# sb-sonata-hyperram.net
KiCad netlist of a schematic drawn in Altium Designer
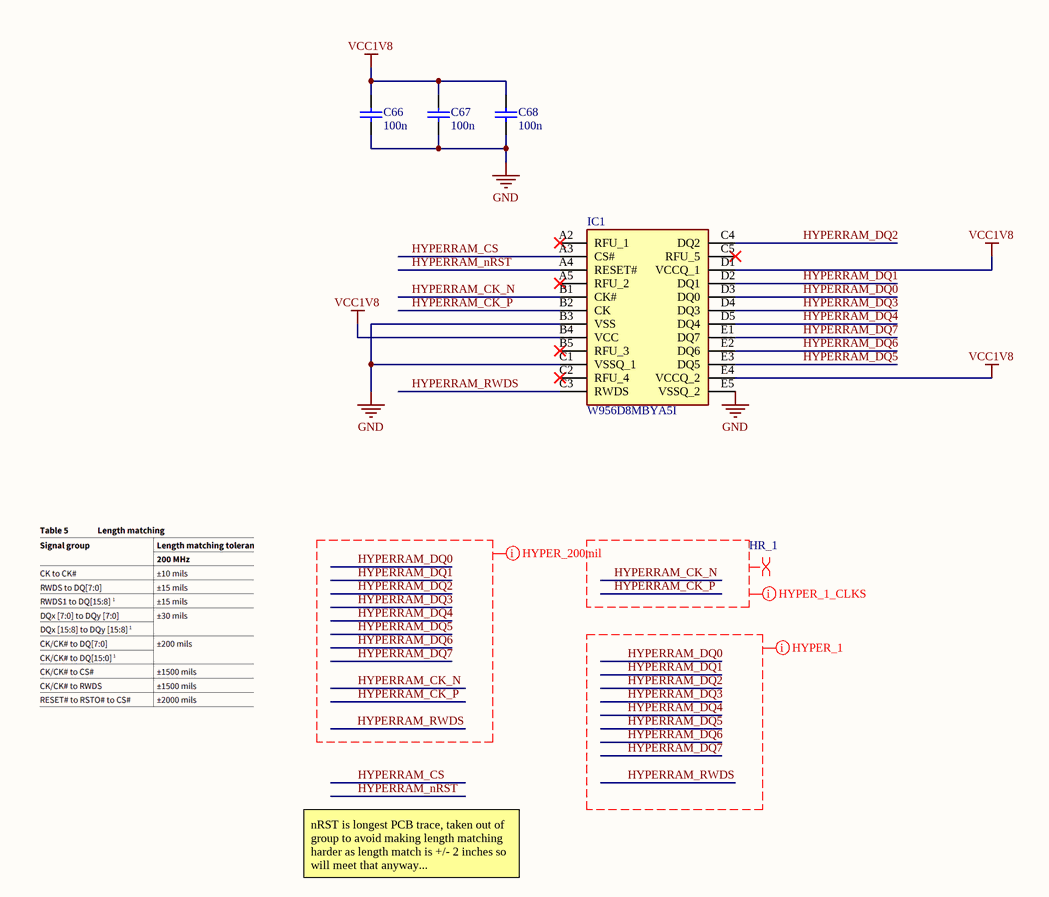
[diagram p0: sb-sonata-hyperram.SchDoc]

(export (version "E")
  (design (tool "Eeschema 10.0.6"))
  (components
    (comp (ref "C66")
      (value "100n")
      (footprint "CAPC0402_M")
      (description "100n, 0402")
      (fields (field (name "PART NUMBER") "CCHIP-100n-0402"))
      (libsource (lib "NewAE_AltiumLib") (part "CAP"))
    )
    (comp (ref "C67")
      (value "100n")
      (footprint "CAPC0402_M")
      (description "100n, 0402")
      (fields (field (name "PART NUMBER") "CCHIP-100n-0402"))
      (libsource (lib "NewAE_AltiumLib") (part "CAP"))
    )
    (comp (ref "C68")
      (value "100n")
      (footprint "CAPC0402_M")
      (description "100n, 0402")
      (fields (field (name "PART NUMBER") "CCHIP-100n-0402"))
      (libsource (lib "NewAE_AltiumLib") (part "CAP"))
    )
    (comp (ref "IC1")
      (value "W956D8MBYA5I")
      (footprint "BGA24C100P5X5_600X800X120")
      (description "Integrated Circuit")
      (fields (field (name "MOUSER PART NUMBER") "454-W956D8MBYA5I"))
      (libsource (lib "*") (part "W956D8MBYA5I"))
    )
  )
  (nets
    (net (code "1") (name "/HYPERRAM_CK_N") (class "Default")
      (node (ref "IC1") (pin "B1") (pinfunction "CK#_B1") (pintype "passive"))
    )
    (net (code "2") (name "/HYPERRAM_CK_P") (class "Default")
      (node (ref "IC1") (pin "B2") (pinfunction "CK_B2") (pintype "passive"))
    )
    (net (code "3") (name "/HYPERRAM_CS") (class "Default")
      (node (ref "IC1") (pin "A3") (pinfunction "CS#_A3") (pintype "passive"))
    )
    (net (code "4") (name "/HYPERRAM_DQ0") (class "Default")
      (node (ref "IC1") (pin "D3") (pinfunction "DQ0_D3") (pintype "passive"))
    )
    (net (code "5") (name "/HYPERRAM_DQ1") (class "Default")
      (node (ref "IC1") (pin "D2") (pinfunction "DQ1_D2") (pintype "passive"))
    )
    (net (code "6") (name "/HYPERRAM_DQ2") (class "Default")
      (node (ref "IC1") (pin "C4") (pinfunction "DQ2_C4") (pintype "passive"))
    )
    (net (code "7") (name "/HYPERRAM_DQ3") (class "Default")
      (node (ref "IC1") (pin "D4") (pinfunction "DQ3_D4") (pintype "passive"))
    )
    (net (code "8") (name "/HYPERRAM_DQ4") (class "Default")
      (node (ref "IC1") (pin "D5") (pinfunction "DQ4_D5") (pintype "passive"))
    )
    (net (code "9") (name "/HYPERRAM_DQ5") (class "Default")
      (node (ref "IC1") (pin "E3") (pinfunction "DQ5_E3") (pintype "passive"))
    )
    (net (code "10") (name "/HYPERRAM_DQ6") (class "Default")
      (node (ref "IC1") (pin "E2") (pinfunction "DQ6_E2") (pintype "passive"))
    )
    (net (code "11") (name "/HYPERRAM_DQ7") (class "Default")
      (node (ref "IC1") (pin "E1") (pinfunction "DQ7_E1") (pintype "passive"))
    )
    (net (code "12") (name "/HYPERRAM_RWDS") (class "Default")
      (node (ref "IC1") (pin "C3") (pinfunction "RWDS_C3") (pintype "passive"))
    )
    (net (code "13") (name "/HYPERRAM_nRST") (class "Default")
      (node (ref "IC1") (pin "A4") (pinfunction "RESET#_A4") (pintype "passive"))
    )
    (net (code "14") (name "GND") (class "Default")
      (node (ref "C66") (pin "2") (pinfunction "2_2") (pintype "passive"))
      (node (ref "C67") (pin "2") (pinfunction "2_2") (pintype "passive"))
      (node (ref "C68") (pin "2") (pinfunction "2_2") (pintype "passive"))
      (node (ref "IC1") (pin "B3") (pinfunction "VSS_B3") (pintype "passive"))
      (node (ref "IC1") (pin "C1") (pinfunction "VSSQ_1_C1") (pintype "passive"))
      (node (ref "IC1") (pin "E5") (pinfunction "VSSQ_2_E5") (pintype "passive"))
    )
    (net (code "15") (name "VCC1V8") (class "Default")
      (node (ref "C66") (pin "1") (pinfunction "1_1") (pintype "passive"))
      (node (ref "C67") (pin "1") (pinfunction "1_1") (pintype "passive"))
      (node (ref "C68") (pin "1") (pinfunction "1_1") (pintype "passive"))
      (node (ref "IC1") (pin "B4") (pinfunction "VCC_B4") (pintype "passive"))
      (node (ref "IC1") (pin "D1") (pinfunction "VCCQ_1_D1") (pintype "passive"))
      (node (ref "IC1") (pin "E4") (pinfunction "VCCQ_2_E4") (pintype "passive"))
    )
    (net (code "16") (name "unconnected-(IC1-RFU_1-PadA2)") (class "Default")
      (node (ref "IC1") (pin "A2") (pinfunction "RFU_1_A2") (pintype "passive+no_connect"))
    )
    (net (code "17") (name "unconnected-(IC1-RFU_2-PadA5)") (class "Default")
      (node (ref "IC1") (pin "A5") (pinfunction "RFU_2_A5") (pintype "passive+no_connect"))
    )
    (net (code "18") (name "unconnected-(IC1-RFU_3-PadB5)") (class "Default")
      (node (ref "IC1") (pin "B5") (pinfunction "RFU_3_B5") (pintype "passive+no_connect"))
    )
    (net (code "19") (name "unconnected-(IC1-RFU_4-PadC2)") (class "Default")
      (node (ref "IC1") (pin "C2") (pinfunction "RFU_4_C2") (pintype "passive+no_connect"))
    )
    (net (code "20") (name "unconnected-(IC1-RFU_5-PadC5)") (class "Default")
      (node (ref "IC1") (pin "C5") (pinfunction "RFU_5_C5") (pintype "passive+no_connect"))
    )
  )
)
